# eagle-schematic.net
KiCad netlist of a schematic drawn in EAGLE
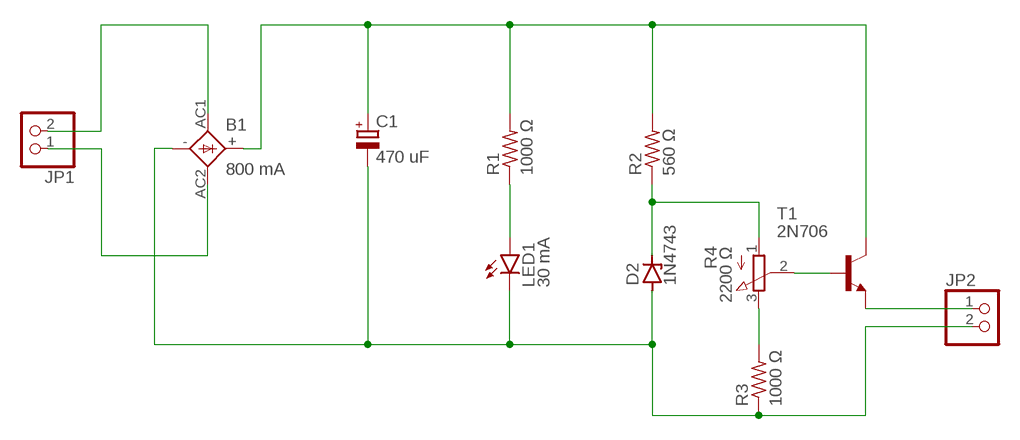
[diagram p0: schematic, sheet 1]

(export (version "E")
  (design (tool "Eeschema 10.0.6"))
  (components
    (comp (ref "B1")
      (value "800 mA")
      (footprint "eagle-import:1KAB")
      (libsource (lib "eagle-import") (part "1KAB"))
    )
    (comp (ref "C1")
      (value "470 uF")
      (footprint "eagle-import:E3,5-10")
      (libsource (lib "eagle-import") (part "CPOL-EUE3.5-10"))
    )
    (comp (ref "D2")
      (value "1N4743")
      (footprint "eagle-import:ZDIO12.5")
      (libsource (lib "eagle-import") (part "ZENER-DIODEZD-12.5"))
    )
    (comp (ref "JP1")
      (value "PINHD-1X2")
      (footprint "eagle-import:1X02")
      (libsource (lib "eagle-import") (part "PINHD-1X2"))
    )
    (comp (ref "JP2")
      (value "PINHD-1X2")
      (footprint "eagle-import:1X02")
      (libsource (lib "eagle-import") (part "PINHD-1X2"))
    )
    (comp (ref "LED1")
      (value "30 mA")
      (footprint "eagle-import:LED5MM")
      (libsource (lib "eagle-import") (part "LED5MM"))
    )
    (comp (ref "R1")
      (value "1000 Ω")
      (footprint "eagle-import:0309_12")
      (libsource (lib "eagle-import") (part "R-US_0309/12"))
    )
    (comp (ref "R2")
      (value "560 Ω")
      (footprint "eagle-import:0309_12")
      (libsource (lib "eagle-import") (part "R-US_0309/12"))
    )
    (comp (ref "R3")
      (value "1000 Ω")
      (footprint "eagle-import:0309_12")
      (libsource (lib "eagle-import") (part "R-US_0309/12"))
    )
    (comp (ref "R4")
      (value "2200 Ω")
      (footprint "eagle-import:3RP_1610N")
      (libsource (lib "eagle-import") (part "3RP/1610N"))
    )
    (comp (ref "T1")
      (value "2N706")
      (footprint "eagle-import:TO18")
      (libsource (lib "eagle-import") (part "2N706"))
    )
  )
  (nets
    (net (code "1") (name "Net-(B1-PadAC1)") (class "Default")
      (node (ref "B1") (pin "AC1") (pinfunction "AC1_AC1") (pintype "passive"))
      (node (ref "JP1") (pin "2") (pinfunction "2_2") (pintype "passive"))
    )
    (net (code "2") (name "Net-(B1-PadAC2)") (class "Default")
      (node (ref "B1") (pin "AC2") (pinfunction "AC2_AC2") (pintype "passive"))
      (node (ref "JP1") (pin "1") (pinfunction "1_1") (pintype "passive"))
    )
    (net (code "3") (name "Net-(LED1-C)") (class "Default")
      (node (ref "B1") (pin "-") (pinfunction "-_-") (pintype "passive"))
      (node (ref "C1") (pin "-") (pinfunction "-_-") (pintype "passive"))
      (node (ref "D2") (pin "A") (pinfunction "A_A") (pintype "passive"))
      (node (ref "JP2") (pin "2") (pinfunction "2_2") (pintype "passive"))
      (node (ref "LED1") (pin "K") (pinfunction "C_K") (pintype "passive"))
      (node (ref "R3") (pin "1") (pinfunction "1_1") (pintype "passive"))
    )
    (net (code "4") (name "Net-(LED1-PadA)") (class "Default")
      (node (ref "LED1") (pin "A") (pinfunction "A_A") (pintype "passive"))
      (node (ref "R1") (pin "1") (pinfunction "1_1") (pintype "passive"))
    )
    (net (code "5") (name "Net-(R4-A)") (class "Default")
      (node (ref "D2") (pin "C") (pinfunction "C_C") (pintype "passive"))
      (node (ref "R2") (pin "1") (pinfunction "1_1") (pintype "passive"))
      (node (ref "R4") (pin "1") (pinfunction "A_1") (pintype "passive"))
    )
    (net (code "6") (name "Net-(R4-E)") (class "Default")
      (node (ref "R3") (pin "2") (pinfunction "2_2") (pintype "passive"))
      (node (ref "R4") (pin "3") (pinfunction "E_3") (pintype "passive"))
    )
    (net (code "7") (name "Net-(R4-S)") (class "Default")
      (node (ref "R4") (pin "2") (pinfunction "S_2") (pintype "passive"))
      (node (ref "T1") (pin "2") (pinfunction "B_2") (pintype "passive"))
    )
    (net (code "8") (name "Net-(T1-C)") (class "Default")
      (node (ref "B1") (pin "+") (pinfunction "+_+") (pintype "passive"))
      (node (ref "C1") (pin "+") (pinfunction "+_+") (pintype "passive"))
      (node (ref "R1") (pin "2") (pinfunction "2_2") (pintype "passive"))
      (node (ref "R2") (pin "2") (pinfunction "2_2") (pintype "passive"))
      (node (ref "T1") (pin "3") (pinfunction "C_3") (pintype "passive"))
    )
    (net (code "9") (name "Net-(T1-E)") (class "Default")
      (node (ref "JP2") (pin "1") (pinfunction "1_1") (pintype "passive"))
      (node (ref "T1") (pin "1") (pinfunction "E_1") (pintype "passive"))
    )
  )
)
